# MKRZero_V5_0.net
KiCad netlist of a schematic drawn in EAGLE
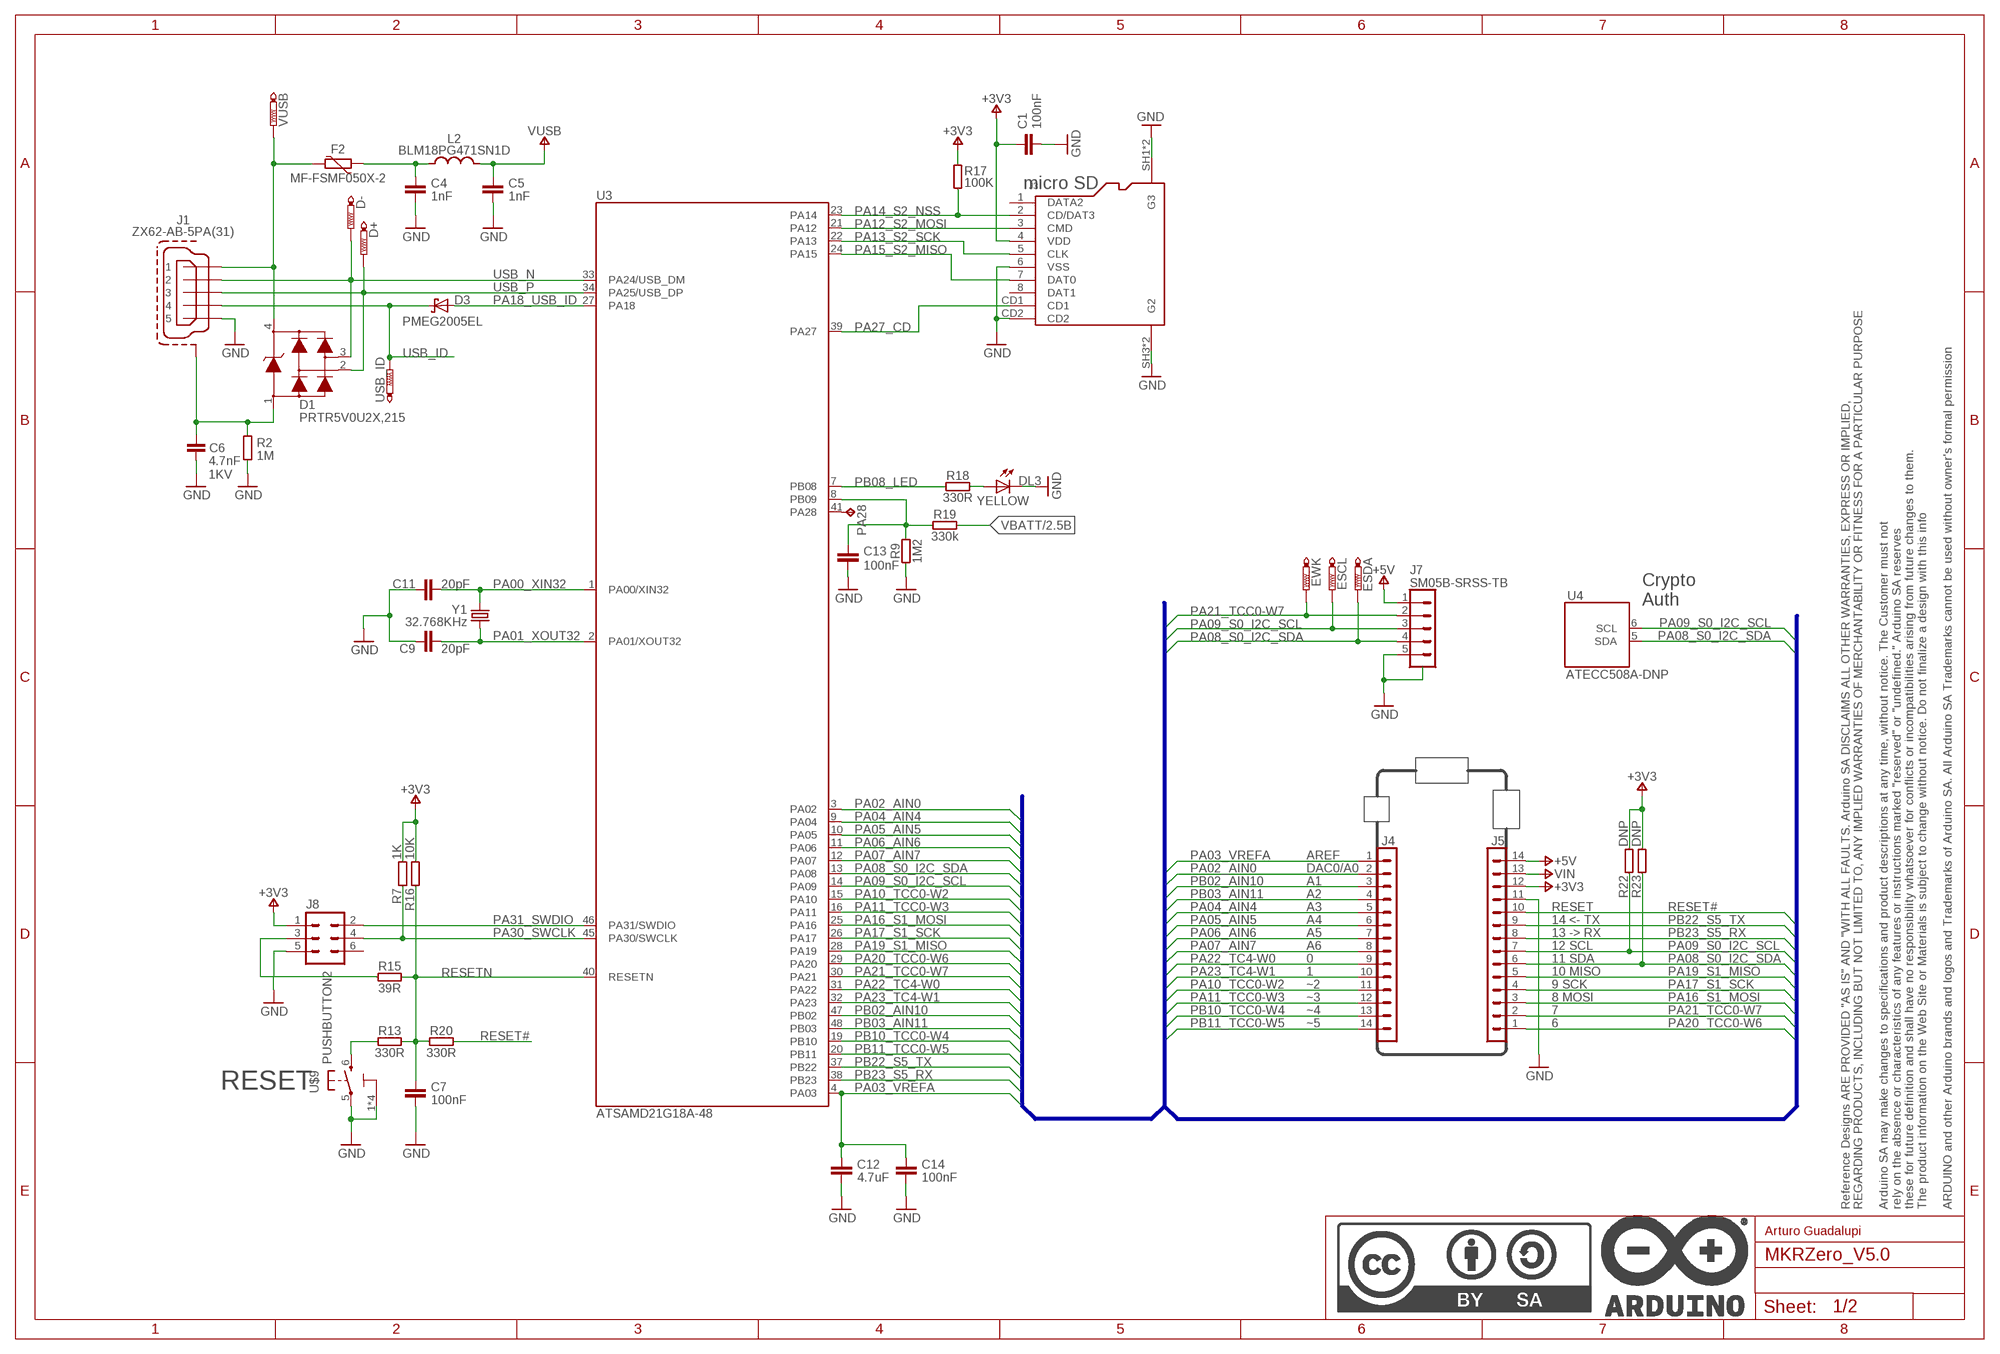
[diagram p0: schematic, sheet 1]
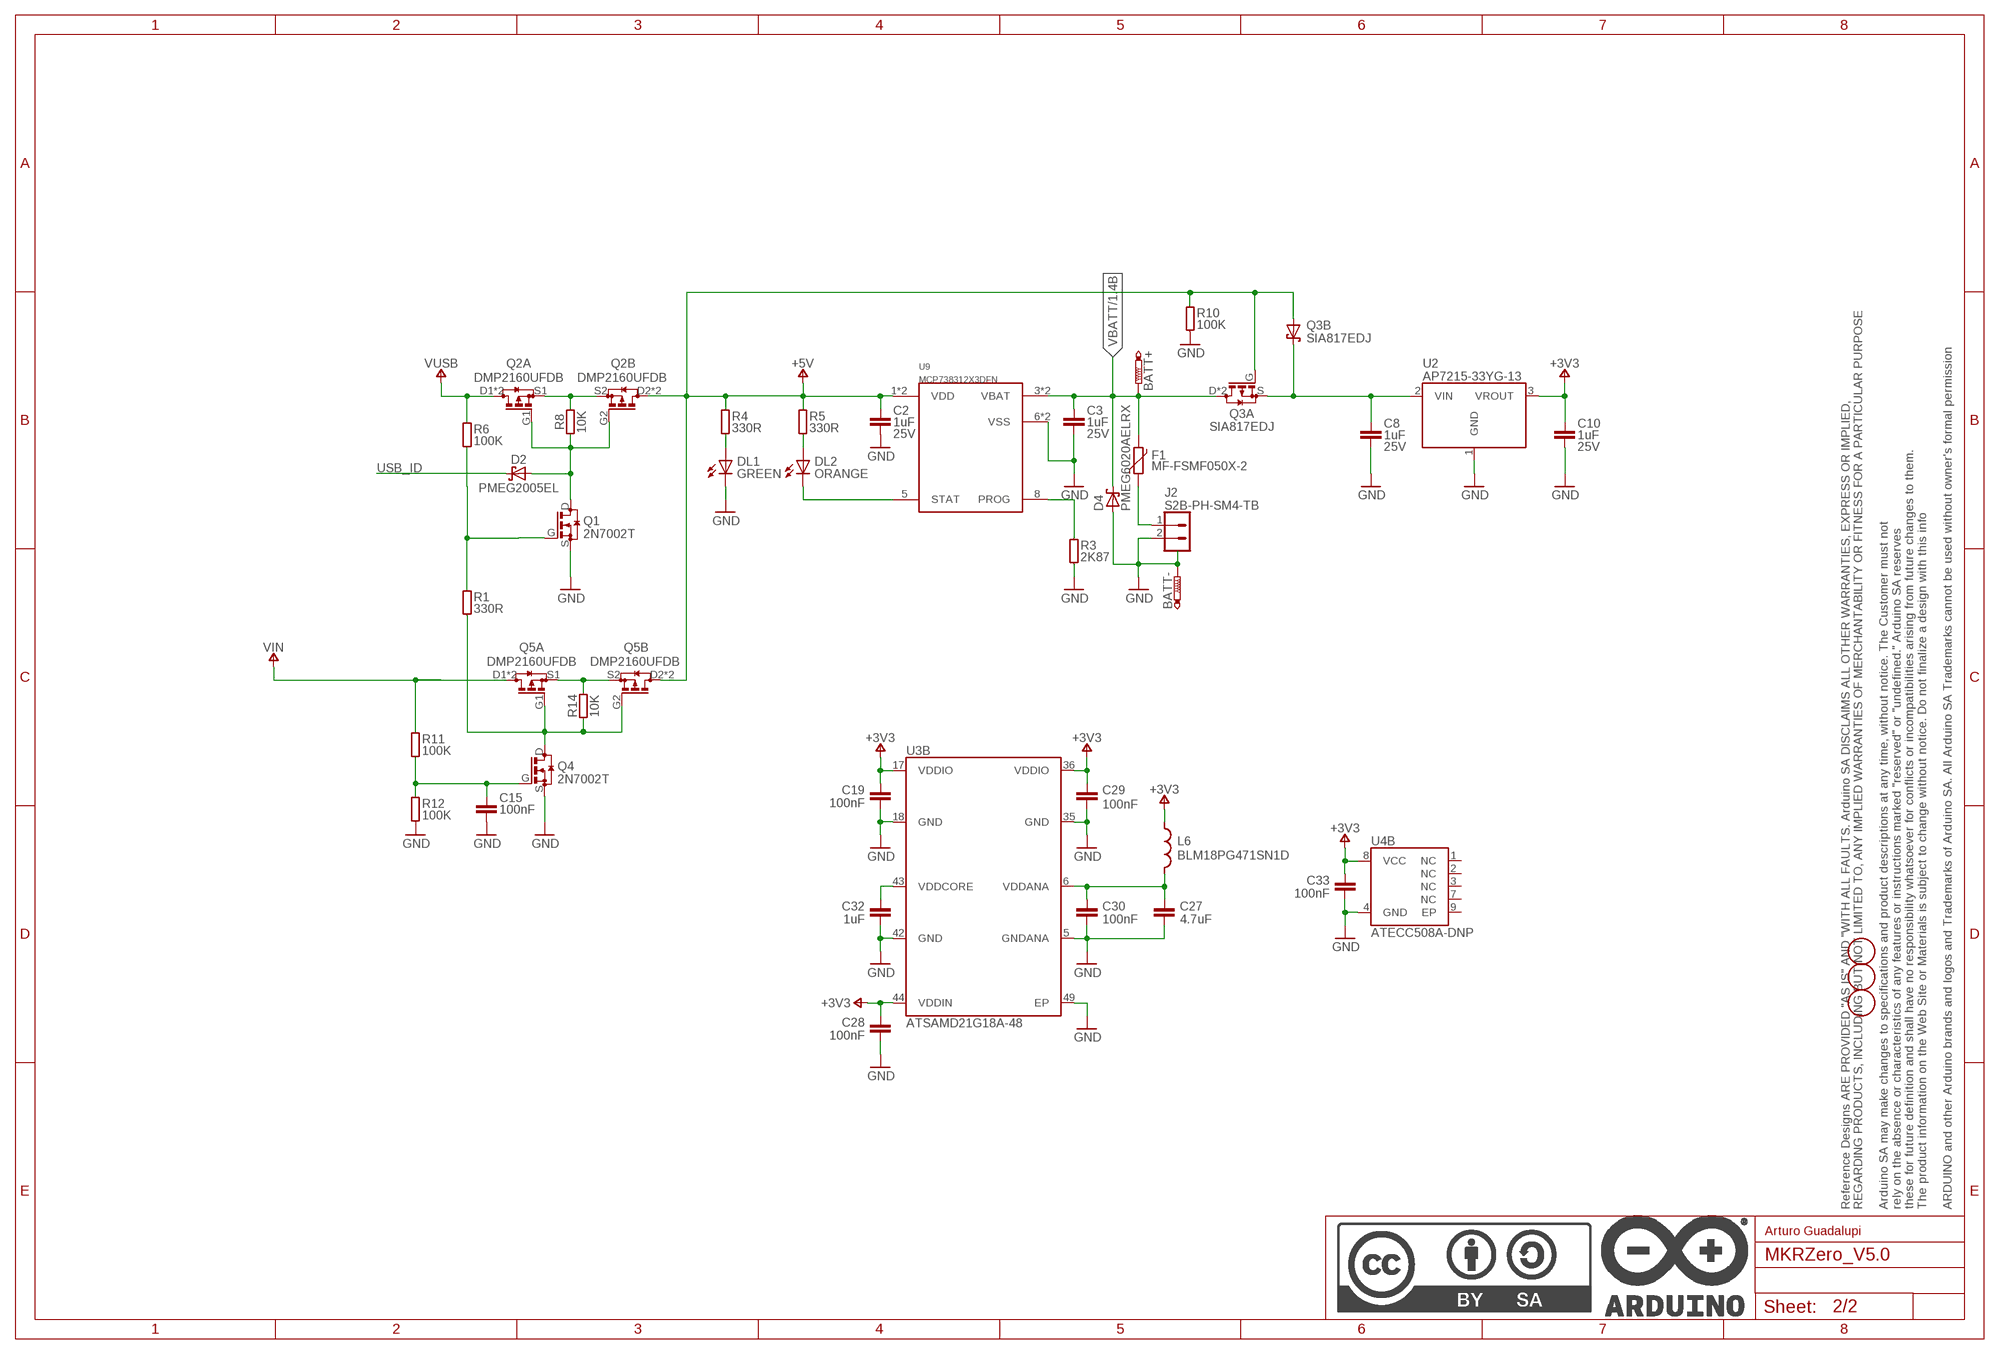
[diagram p1: schematic, sheet 2]

(export (version "E")
  (design (tool "Eeschema 10.0.6"))
  (components
    (comp (ref "BATT+")
      (value "PTR1B1,27")
      (footprint "eagle-import:B1,27")
      (libsource (lib "eagle-import") (part "PTR1B1,27"))
    )
    (comp (ref "BATT-")
      (value "PTR1B1,27")
      (footprint "eagle-import:B1,27")
      (libsource (lib "eagle-import") (part "PTR1B1,27"))
    )
    (comp (ref "C2")
      (value "1uF")
      (footprint "eagle-import:0402-1005X55N")
      (fields
        (field (name "MF") "Murata")
        (field (name "MPN") "GRM155R61E105KA12D ")
        (field (name "VOLTAGE") "25V")
      )
      (libsource (lib "eagle-import") (part "C-0402-1UF"))
    )
    (comp (ref "C3")
      (value "1uF")
      (footprint "eagle-import:0402-1005X55N")
      (fields
        (field (name "MF") "Murata")
        (field (name "MPN") "GRM155R61E105KA12D ")
        (field (name "VOLTAGE") "25V")
      )
      (libsource (lib "eagle-import") (part "C-0402-1UF"))
    )
    (comp (ref "C8")
      (value "1uF")
      (footprint "eagle-import:0402-1005X55N")
      (fields
        (field (name "MF") "Murata")
        (field (name "MPN") "GRM155R61E105KA12D ")
        (field (name "VOLTAGE") "25V")
      )
      (libsource (lib "eagle-import") (part "C-0402-1UF"))
    )
    (comp (ref "C10")
      (value "1uF")
      (footprint "eagle-import:0402-1005X55N")
      (fields
        (field (name "MF") "Murata")
        (field (name "MPN") "GRM155R61E105KA12D ")
        (field (name "VOLTAGE") "25V")
      )
      (libsource (lib "eagle-import") (part "C-0402-1UF"))
    )
    (comp (ref "C15")
      (value "100nF")
      (footprint "eagle-import:0402-1005X55N")
      (fields
        (field (name "MF") "Murata")
        (field (name "MPN") "GRM155R61E105KA12D ")
        (field (name "VOLTAGE") "25V")
      )
      (libsource (lib "eagle-import") (part "C-0402-1UF"))
    )
    (comp (ref "C19")
      (value "100nF")
      (footprint "eagle-import:0402-1005X55N")
      (fields (field (name "MF") "TDK") (field (name "MPN") "C1005X5R1H104K050BB "))
      (libsource (lib "eagle-import") (part "C-0402-100NF"))
    )
    (comp (ref "C27")
      (value "4.7uF")
      (footprint "eagle-import:0402-1005X55N")
      (fields (field (name "MF") "Murata") (field (name "MPN") "GRM155R60J475ME47D "))
      (libsource (lib "eagle-import") (part "C-0402-4.7UF"))
    )
    (comp (ref "C28")
      (value "100nF")
      (footprint "eagle-import:0402-1005X55N")
      (fields (field (name "MF") "TDK") (field (name "MPN") "C1005X5R1H104K050BB "))
      (libsource (lib "eagle-import") (part "C-0402-100NF"))
    )
    (comp (ref "C29")
      (value "100nF")
      (footprint "eagle-import:0402-1005X55N")
      (fields (field (name "MF") "TDK") (field (name "MPN") "C1005X5R1H104K050BB "))
      (libsource (lib "eagle-import") (part "C-0402-100NF"))
    )
    (comp (ref "C30")
      (value "100nF")
      (footprint "eagle-import:0402-1005X55N")
      (fields (field (name "MF") "TDK") (field (name "MPN") "C1005X5R1H104K050BB "))
      (libsource (lib "eagle-import") (part "C-0402-100NF"))
    )
    (comp (ref "C32")
      (value "1uF")
      (footprint "eagle-import:0402-1005X55N")
      (fields (field (name "MF") "Murata") (field (name "MPN") "GRM155R61E105KA12D "))
      (libsource (lib "eagle-import") (part "C-0402-1UF"))
    )
    (comp (ref "C33")
      (value "100nF")
      (footprint "eagle-import:0402-1005X55N")
      (fields (field (name "MF") "TDK") (field (name "MPN") "C1005X5R1H104K050BB "))
      (libsource (lib "eagle-import") (part "C-0402-100NF"))
    )
    (comp (ref "D2")
      (value "PMEG2005EL")
      (footprint "eagle-import:SODFL1008X40N-882D")
      (fields (field (name "MF") "NXP") (field (name "MPN") "PMEG2005EL,315 "))
      (libsource (lib "eagle-import") (part "PMEG2005EL"))
    )
    (comp (ref "D4")
      (value "PMEG6020AELRX")
      (footprint "eagle-import:SMA_DO123")
      (libsource (lib "eagle-import") (part "D_SCHOTTKYSO123"))
    )
    (comp (ref "DL1")
      (value "GREEN")
      (footprint "eagle-import:LEDC1608X80N-AK")
      (fields (field (name "MF") "Avago ") (field (name "MPN") "HSMG-C190 "))
      (libsource (lib "eagle-import") (part "LED-0603-GREEN"))
    )
    (comp (ref "DL2")
      (value "ORANGE")
      (footprint "eagle-import:LEDC1608X80N-AK")
      (fields (field (name "MF") "Avago ") (field (name "MPN") "HSMD-C190 "))
      (libsource (lib "eagle-import") (part "LED-0603-ORANGE"))
    )
    (comp (ref "F1")
      (value "MF-FSMF050X-2")
      (footprint "eagle-import:0603-F1608X100N")
      (fields (field (name "MF") "Bourns Inc ") (field (name "MPN") "MF-FSMF050X-2 "))
      (libsource (lib "eagle-import") (part "MF-FSMF050X-2"))
    )
    (comp (ref "FD1")
      (value "FIDUCIALMOUNT")
      (footprint "eagle-import:FIDUCIAL-MOUNT")
      (libsource (lib "eagle-import") (part "FIDUCIALMOUNT"))
    )
    (comp (ref "FD2")
      (value "FIDUCIALMOUNT")
      (footprint "eagle-import:FIDUCIAL-MOUNT")
      (libsource (lib "eagle-import") (part "FIDUCIALMOUNT"))
    )
    (comp (ref "FD3")
      (value "FIDUCIALMOUNT")
      (footprint "eagle-import:FIDUCIAL-MOUNT")
      (libsource (lib "eagle-import") (part "FIDUCIALMOUNT"))
    )
    (comp (ref "FRAME2")
      (value "DNP")
      (footprint "eagle-import:FRAME")
      (libsource (lib "eagle-import") (part "A3-FRAME"))
    )
    (comp (ref "J2")
      (value "S2B-PH-SM4-TB")
      (footprint "eagle-import:JST-S2B-PH-SM4-TB")
      (fields (field (name "MF") "JST ") (field (name "MPN") "S2B-PH-SM4-TB(LF)(SN) "))
      (libsource (lib "eagle-import") (part "S2B-PH-SM4-TB"))
    )
    (comp (ref "L6")
      (value "BLM18PG471SN1D")
      (footprint "eagle-import:0603-1608X90N")
      (libsource (lib "eagle-import") (part "BLM18PG471SN1D"))
    )
    (comp (ref "Q1")
      (value "2N7002T")
      (footprint "eagle-import:SOTFL50P160X78-3")
      (fields (field (name "MF") "Fairchild"))
      (libsource (lib "eagle-import") (part "2N7002T"))
    )
    (comp (ref "Q2")
      (value "DMP2160UFDB")
      (footprint "eagle-import:SON65P200X200X60-8N-DM")
      (fields (field (name "MF") "Diodes Inc ") (field (name "MPN") "DMP2160UFDB-7 "))
      (libsource (lib "eagle-import") (part "DMP2160UFDB"))
    )
    (comp (ref "Q3")
      (value "SIA817EDJ")
      (footprint "eagle-import:SON65P205X205X75-8N-MWSD")
      (fields (field (name "MF") "Vishay ") (field (name "MPN") "SIA817EDJ-T1-GE3 "))
      (libsource (lib "eagle-import") (part "SIA817EDJ"))
    )
    (comp (ref "Q4")
      (value "2N7002T")
      (footprint "eagle-import:SOTFL50P160X78-3")
      (fields (field (name "MF") "Fairchild"))
      (libsource (lib "eagle-import") (part "2N7002T"))
    )
    (comp (ref "Q5")
      (value "DMP2160UFDB")
      (footprint "eagle-import:SON65P200X200X60-8N-DM")
      (fields (field (name "MF") "Diodes Inc ") (field (name "MPN") "DMP2160UFDB-7 "))
      (libsource (lib "eagle-import") (part "DMP2160UFDB"))
    )
    (comp (ref "R1")
      (value "330R")
      (footprint "eagle-import:0402-1005X55N")
      (fields (field (name "MF") "Yageo ") (field (name "MPN") "RC0402FR-07330RL "))
      (libsource (lib "eagle-import") (part "R-0402-330R"))
    )
    (comp (ref "R3")
      (value "2K87")
      (footprint "eagle-import:0402-1005X55N")
      (fields (field (name "MF") "Yageo") (field (name "MPN") "RC0402FR-072K87L"))
      (libsource (lib "eagle-import") (part "R-0402-2K87"))
    )
    (comp (ref "R4")
      (value "330R")
      (footprint "eagle-import:0402-1005X55N")
      (fields (field (name "MF") "Yageo ") (field (name "MPN") "RC0402FR-07330RL "))
      (libsource (lib "eagle-import") (part "R-0402-330R"))
    )
    (comp (ref "R5")
      (value "330R")
      (footprint "eagle-import:0402-1005X55N")
      (fields (field (name "MF") "Yageo ") (field (name "MPN") "RC0402FR-07330RL "))
      (libsource (lib "eagle-import") (part "R-0402-330R"))
    )
    (comp (ref "R6")
      (value "100K")
      (footprint "eagle-import:0402-1005X55N")
      (fields (field (name "MF") "Yageo ") (field (name "MPN") "RC0402FR-07100KL "))
      (libsource (lib "eagle-import") (part "R-0402-100K"))
    )
    (comp (ref "R8")
      (value "10K")
      (footprint "eagle-import:0402-1005X55N")
      (fields (field (name "MF") "Yageo") (field (name "MPN") "RC0402FR-0710KL"))
      (libsource (lib "eagle-import") (part "R-0402-10K"))
    )
    (comp (ref "R10")
      (value "100K")
      (footprint "eagle-import:0402-1005X55N")
      (fields (field (name "MF") "Yageo ") (field (name "MPN") "RC0402FR-07100KL "))
      (libsource (lib "eagle-import") (part "R-0402-100K"))
    )
    (comp (ref "R11")
      (value "100K")
      (footprint "eagle-import:0402-1005X55N")
      (fields (field (name "MF") "Yageo ") (field (name "MPN") "RC0402FR-07100KL "))
      (libsource (lib "eagle-import") (part "R-0402-100K"))
    )
    (comp (ref "R12")
      (value "100K")
      (footprint "eagle-import:0402-1005X55N")
      (fields (field (name "MF") "Yageo ") (field (name "MPN") "RC0402FR-07100KL "))
      (libsource (lib "eagle-import") (part "R-0402-100K"))
    )
    (comp (ref "R14")
      (value "10K")
      (footprint "eagle-import:0402-1005X55N")
      (fields (field (name "MF") "Yageo") (field (name "MPN") "RC0402FR-0710KL"))
      (libsource (lib "eagle-import") (part "R-0402-10K"))
    )
    (comp (ref "U2")
      (value "AP7215-33YG-13")
      (footprint "eagle-import:SOT150P400X160-3N")
      (fields (field (name "MF") "Diodes Inc ") (field (name "MPN") "AP7215-33YG-13 "))
      (libsource (lib "eagle-import") (part "AP7215-33YG-13"))
    )
    (comp (ref "U3")
      (value "ATSAMD21G18A-48")
      (footprint "eagle-import:QFN50P700X700X90-49XN-EPSQ515")
      (fields (field (name "MF") "Atmel") (field (name "MPN") "ATSAMD21E18A-MU "))
      (libsource (lib "eagle-import") (part "ATSAMD21G18A-48"))
    )
    (comp (ref "U4")
      (value "ATECC508A-DNP")
      (footprint "eagle-import:SON50P300X200X60-9N-EP160X140")
      (fields (field (name "MF") "Atmel") (field (name "MPN") "ATECC508A-MAHDA-T "))
      (libsource (lib "eagle-import") (part "ATECC508A-MAHDA-T"))
    )
    (comp (ref "U9")
      (value "MCP738312X3DFN")
      (footprint "eagle-import:2X3DFN")
      (libsource (lib "eagle-import") (part "MCP738312X3DFN"))
    )
    (comp (ref "C1")
      (value "100nF")
      (footprint "eagle-import:0402-1005X55N")
      (fields (field (name "MF") "TDK") (field (name "MPN") "C1005X5R1H104K050BB "))
      (libsource (lib "eagle-import") (part "C-0402-100NF"))
    )
    (comp (ref "C4")
      (value "1nF")
      (footprint "eagle-import:0402-1005X55N")
      (fields (field (name "MF") "Murata ") (field (name "MPN") "GRM155R71H103KA88J "))
      (libsource (lib "eagle-import") (part "C-0402-10NF"))
    )
    (comp (ref "C5")
      (value "1nF")
      (footprint "eagle-import:0402-1005X55N")
      (fields (field (name "MF") "TDK") (field (name "MPN") "C1005X5R1H104K050BB "))
      (libsource (lib "eagle-import") (part "C-0402-100NF"))
    )
    (comp (ref "C6")
      (value "4.7nF")
      (footprint "eagle-import:C0805")
      (fields (field (name "VOLTAGE") "1KV"))
      (libsource (lib "eagle-import") (part "CAPACITORS-0805"))
    )
    (comp (ref "C7")
      (value "100nF")
      (footprint "eagle-import:0402-1005X55N")
      (fields (field (name "MF") "TDK") (field (name "MPN") "C1005X5R1H104K050BB "))
      (libsource (lib "eagle-import") (part "C-0402-100NF"))
    )
    (comp (ref "C9")
      (value "20pF")
      (footprint "eagle-import:0402-1005X55N")
      (fields (field (name "MF") "Kemet") (field (name "MPN") "CBR04C200J5GAC "))
      (libsource (lib "eagle-import") (part "C-0402-20PF"))
    )
    (comp (ref "C11")
      (value "20pF")
      (footprint "eagle-import:0402-1005X55N")
      (fields (field (name "MF") "Kemet") (field (name "MPN") "CBR04C200J5GAC "))
      (libsource (lib "eagle-import") (part "C-0402-20PF"))
    )
    (comp (ref "C12")
      (value "4.7uF")
      (footprint "eagle-import:0402-1005X55N")
      (fields (field (name "MF") "Murata") (field (name "MPN") "GRM155R60J475ME47D "))
      (libsource (lib "eagle-import") (part "C-0402-4.7UF"))
    )
    (comp (ref "C13")
      (value "100nF")
      (footprint "eagle-import:0402-1005X55N")
      (fields (field (name "MF") "TDK") (field (name "MPN") "C1005X5R1H104K050BB "))
      (libsource (lib "eagle-import") (part "C-0402-100NF"))
    )
    (comp (ref "C14")
      (value "100nF")
      (footprint "eagle-import:0402-1005X55N")
      (fields (field (name "MF") "TDK") (field (name "MPN") "C1005X5R1H104K050BB "))
      (libsource (lib "eagle-import") (part "C-0402-100NF"))
    )
    (comp (ref "D+")
      (value "PTR1B1,27")
      (footprint "eagle-import:B1,27")
      (libsource (lib "eagle-import") (part "PTR1B1,27"))
    )
    (comp (ref "D-")
      (value "PTR1B1,27")
      (footprint "eagle-import:B1,27")
      (libsource (lib "eagle-import") (part "PTR1B1,27"))
    )
    (comp (ref "D1")
      (value "PRTR5V0U2X,215")
      (footprint "eagle-import:SOT190P230X110-4N")
      (fields (field (name "MF") "NXP") (field (name "MPN") "PRTR5V0U2X,215 "))
      (libsource (lib "eagle-import") (part "PRTR5V0U2X,215"))
    )
    (comp (ref "D3")
      (value "PMEG2005EL")
      (footprint "eagle-import:SODFL1008X40N-882D")
      (fields (field (name "MF") "NXP") (field (name "MPN") "PMEG2005EL,315 "))
      (libsource (lib "eagle-import") (part "PMEG2005EL"))
    )
    (comp (ref "DL3")
      (value "YELLOW")
      (footprint "eagle-import:LEDC1608X80N-AK")
      (fields (field (name "MF") "Avago ") (field (name "MPN") "HSMG-C190 "))
      (libsource (lib "eagle-import") (part "LED-0603-GREEN"))
    )
    (comp (ref "ESCL")
      (value "PTR1B1,27")
      (footprint "eagle-import:B1,27")
      (libsource (lib "eagle-import") (part "PTR1B1,27"))
    )
    (comp (ref "ESDA")
      (value "PTR1B1,27")
      (footprint "eagle-import:B1,27")
      (libsource (lib "eagle-import") (part "PTR1B1,27"))
    )
    (comp (ref "EWK")
      (value "PTR1B1,27")
      (footprint "eagle-import:B1,27")
      (libsource (lib "eagle-import") (part "PTR1B1,27"))
    )
    (comp (ref "F2")
      (value "MF-FSMF050X-2")
      (footprint "eagle-import:0603-F1608X100N")
      (fields (field (name "MF") "Bourns Inc ") (field (name "MPN") "MF-FSMF050X-2 "))
      (libsource (lib "eagle-import") (part "MF-FSMF050X-2"))
    )
    (comp (ref "FRAME1")
      (value "DNP")
      (footprint "eagle-import:FRAME")
      (libsource (lib "eagle-import") (part "A3-FRAME"))
    )
    (comp (ref "J1")
      (value "ZX62-AB-5PA(31)")
      (footprint "eagle-import:USBMICRO-ZX62-AB-5PA")
      (libsource (lib "eagle-import") (part "ZX62AB-5PA(11)"))
    )
    (comp (ref "J3")
      (value "AMPHENOL_114-00841-68")
      (footprint "eagle-import:AMPHENOL_114-00841-68")
      (libsource (lib "eagle-import") (part "AMPHENOL_114-00841-68"))
    )
    (comp (ref "J4")
      (value "DNP")
      (footprint "eagle-import:STRIP-14-MODULI-A11")
      (libsource (lib "eagle-import") (part "STRIP-14"))
    )
    (comp (ref "J5")
      (value "DNP")
      (footprint "eagle-import:STRIP-14-MODULI-A11")
      (libsource (lib "eagle-import") (part "STRIP-14"))
    )
    (comp (ref "J7")
      (value "SM05B-SRSS-TB")
      (footprint "eagle-import:SM05B-SRSS-TB")
      (fields (field (name "MF") "JST"))
      (libsource (lib "eagle-import") (part "SM05B-SRSS-TB"))
    )
    (comp (ref "J8")
      (value "2X3_SMD_MALE")
      (footprint "eagle-import:2X3_SMT")
      (libsource (lib "eagle-import") (part "2X3_SMD_MALE"))
    )
    (comp (ref "L2")
      (value "BLM18PG471SN1D")
      (footprint "eagle-import:0603-1608X90N")
      (libsource (lib "eagle-import") (part "BLM18PG471SN1D"))
    )
    (comp (ref "PA28")
      (value "TPB2,54")
      (footprint "eagle-import:B2,54")
      (libsource (lib "eagle-import") (part "TPB2,54"))
    )
    (comp (ref "R2")
      (value "1M")
      (footprint "eagle-import:0402-1005X55N")
      (fields (field (name "MF") "Yageo") (field (name "MPN") "RC0402FR-071ML"))
      (libsource (lib "eagle-import") (part "R-0402-1M"))
    )
    (comp (ref "R7")
      (value "1K")
      (footprint "eagle-import:0402-1005X55N")
      (fields (field (name "MF") "Yageo") (field (name "MPN") "RC0402FR-071KL"))
      (libsource (lib "eagle-import") (part "R-0402-1K"))
    )
    (comp (ref "R9")
      (value "1M2")
      (footprint "eagle-import:0402-1005X55N")
      (fields (field (name "MF") "Yageo ") (field (name "MPN") "RC0402FR-07330RL "))
      (libsource (lib "eagle-import") (part "R-0402-330R"))
    )
    (comp (ref "R13")
      (value "330R")
      (footprint "eagle-import:0402-1005X55N")
      (fields (field (name "MF") "Yageo ") (field (name "MPN") "RC0402FR-07330RL "))
      (libsource (lib "eagle-import") (part "R-0402-330R"))
    )
    (comp (ref "R15")
      (value "39R")
      (footprint "eagle-import:0402-1005X55N")
      (fields (field (name "MF") "Yageo ") (field (name "MPN") "RC0402FR-0739RL "))
      (libsource (lib "eagle-import") (part "R-0402-39R"))
    )
    (comp (ref "R16")
      (value "10K")
      (footprint "eagle-import:0402-1005X55N")
      (fields (field (name "MF") "Yageo") (field (name "MPN") "RC0402FR-0710KL"))
      (libsource (lib "eagle-import") (part "R-0402-10K"))
    )
    (comp (ref "R17")
      (value "100K")
      (footprint "eagle-import:0402-1005X55N")
      (fields (field (name "MF") "Yageo ") (field (name "MPN") "RC0402FR-07100KL "))
      (libsource (lib "eagle-import") (part "R-0402-100K"))
    )
    (comp (ref "R18")
      (value "330R")
      (footprint "eagle-import:0402-1005X55N")
      (fields (field (name "MF") "Yageo ") (field (name "MPN") "RC0402FR-07330RL "))
      (libsource (lib "eagle-import") (part "R-0402-330R"))
    )
    (comp (ref "R19")
      (value "330k")
      (footprint "eagle-import:0402-1005X55N")
      (fields (field (name "MF") "Yageo ") (field (name "MPN") "RC0402FR-07330RL "))
      (libsource (lib "eagle-import") (part "R-0402-330R"))
    )
    (comp (ref "R20")
      (value "330R")
      (footprint "eagle-import:0402-1005X55N")
      (fields (field (name "MF") "Yageo ") (field (name "MPN") "RC0402FR-07330RL "))
      (libsource (lib "eagle-import") (part "R-0402-330R"))
    )
    (comp (ref "R22")
      (value "DNP")
      (footprint "eagle-import:0402-1005X55N")
      (fields (field (name "MF") "Yageo ") (field (name "MPN") "RC0402FR-074K7L "))
      (libsource (lib "eagle-import") (part "R-0402-4K7"))
    )
    (comp (ref "R23")
      (value "DNP")
      (footprint "eagle-import:0402-1005X55N")
      (fields (field (name "MF") "Yageo ") (field (name "MPN") "RC0402FR-074K7L "))
      (libsource (lib "eagle-import") (part "R-0402-4K7"))
    )
    (comp (ref "U$9")
      (value "PUSHBUTTON2")
      (footprint "eagle-import:C&K_PTS820_NOPEGS")
      (libsource (lib "eagle-import") (part "PUSHBUTTON2"))
    )
    (comp (ref "USB_ID")
      (value "PTR1B1,27")
      (footprint "eagle-import:B1,27")
      (libsource (lib "eagle-import") (part "PTR1B1,27"))
    )
    (comp (ref "VUSB")
      (value "PTR1B1,27")
      (footprint "eagle-import:B1,27")
      (libsource (lib "eagle-import") (part "PTR1B1,27"))
    )
    (comp (ref "Y1")
      (value "32.768KHz")
      (footprint "eagle-import:QUARZO-ABS07")
      (fields (field (name "MF") "Abracon ") (field (name "MPN") "ABS07-32.768KHZ-T "))
      (libsource (lib "eagle-import") (part "ABS07-32.768KHZ-T"))
    )
  )
  (nets
    (net (code "1") (name "+3V3") (class "Default")
      (node (ref "C1") (pin "1") (pinfunction "1_1") (pintype "passive"))
      (node (ref "C10") (pin "1") (pinfunction "1_1") (pintype "passive"))
      (node (ref "C19") (pin "1") (pinfunction "1_1") (pintype "passive"))
      (node (ref "C28") (pin "1") (pinfunction "1_1") (pintype "passive"))
      (node (ref "C29") (pin "1") (pinfunction "1_1") (pintype "passive"))
      (node (ref "C33") (pin "1") (pinfunction "1_1") (pintype "passive"))
      (node (ref "J3") (pin "4") (pinfunction "VDD_4") (pintype "power_in"))
      (node (ref "J5") (pin "12") (pinfunction "12_12") (pintype "passive"))
      (node (ref "J8") (pin "1") (pinfunction "1_1") (pintype "passive"))
      (node (ref "L6") (pin "1") (pinfunction "1_1") (pintype "passive"))
      (node (ref "R16") (pin "2") (pinfunction "2_2") (pintype "passive"))
      (node (ref "R17") (pin "2") (pinfunction "2_2") (pintype "passive"))
      (node (ref "R22") (pin "2") (pinfunction "2_2") (pintype "passive"))
      (node (ref "R23") (pin "2") (pinfunction "2_2") (pintype "passive"))
      (node (ref "R7") (pin "2") (pinfunction "2_2") (pintype "passive"))
      (node (ref "U2") (pin "3") (pinfunction "VROUT_3") (pintype "power_in"))
      (node (ref "U3") (pin "17") (pinfunction "VDDIO_17") (pintype "power_in"))
      (node (ref "U3") (pin "36") (pinfunction "VDDIO_36") (pintype "power_in"))
      (node (ref "U3") (pin "44") (pinfunction "VDDIN_44") (pintype "power_in"))
      (node (ref "U4") (pin "8") (pinfunction "VCC_8") (pintype "power_in"))
    )
    (net (code "2") (name "+5V") (class "Default")
      (node (ref "C2") (pin "1") (pinfunction "1_1") (pintype "passive"))
      (node (ref "J5") (pin "14") (pinfunction "14_14") (pintype "passive"))
      (node (ref "J7") (pin "1") (pinfunction "1_1") (pintype "passive"))
      (node (ref "Q2") (pin "D2") (pinfunction "D_D2") (pintype "passive"))
      (node (ref "Q2") (pin "D2'") (pinfunction "D_D2'") (pintype "passive"))
      (node (ref "Q3") (pin "A") (pinfunction "A_A") (pintype "passive"))
      (node (ref "Q3") (pin "G") (pinfunction "G_G") (pintype "passive"))
      (node (ref "Q5") (pin "D2") (pinfunction "D_D2") (pintype "passive"))
      (node (ref "Q5") (pin "D2'") (pinfunction "D_D2'") (pintype "passive"))
      (node (ref "R10") (pin "2") (pinfunction "2_2") (pintype "passive"))
      (node (ref "R4") (pin "2") (pinfunction "2_2") (pintype "passive"))
      (node (ref "R5") (pin "2") (pinfunction "2_2") (pintype "passive"))
      (node (ref "U9") (pin "1") (pinfunction "VDD_1") (pintype "bidirectional"))
      (node (ref "U9") (pin "2") (pinfunction "VDD_2") (pintype "bidirectional"))
    )
    (net (code "3") (name "GND") (class "Default")
      (node (ref "BATT-") (pin "PP") (pinfunction "TP_PP") (pintype "input"))
      (node (ref "C1") (pin "2") (pinfunction "2_2") (pintype "passive"))
      (node (ref "C10") (pin "2") (pinfunction "2_2") (pintype "passive"))
      (node (ref "C11") (pin "1") (pinfunction "1_1") (pintype "passive"))
      (node (ref "C12") (pin "2") (pinfunction "2_2") (pintype "passive"))
      (node (ref "C13") (pin "2") (pinfunction "2_2") (pintype "passive"))
      (node (ref "C14") (pin "2") (pinfunction "2_2") (pintype "passive"))
      (node (ref "C15") (pin "2") (pinfunction "2_2") (pintype "passive"))
      (node (ref "C19") (pin "2") (pinfunction "2_2") (pintype "passive"))
      (node (ref "C2") (pin "2") (pinfunction "2_2") (pintype "passive"))
      (node (ref "C27") (pin "2") (pinfunction "2_2") (pintype "passive"))
      (node (ref "C28") (pin "2") (pinfunction "2_2") (pintype "passive"))
      (node (ref "C29") (pin "2") (pinfunction "2_2") (pintype "passive"))
      (node (ref "C3") (pin "2") (pinfunction "2_2") (pintype "passive"))
      (node (ref "C30") (pin "2") (pinfunction "2_2") (pintype "passive"))
      (node (ref "C32") (pin "2") (pinfunction "2_2") (pintype "passive"))
      (node (ref "C33") (pin "2") (pinfunction "2_2") (pintype "passive"))
      (node (ref "C4") (pin "2") (pinfunction "2_2") (pintype "passive"))
      (node (ref "C5") (pin "2") (pinfunction "2_2") (pintype "passive"))
      (node (ref "C6") (pin "2") (pinfunction "2_2") (pintype "passive"))
      (node (ref "C7") (pin "2") (pinfunction "2_2") (pintype "passive"))
      (node (ref "C8") (pin "2") (pinfunction "2_2") (pintype "passive"))
      (node (ref "C9") (pin "1") (pinfunction "1_1") (pintype "passive"))
      (node (ref "D4") (pin "A") (pinfunction "A_A") (pintype "passive"))
      (node (ref "DL1") (pin "C") (pinfunction "C_C") (pintype "passive"))
      (node (ref "DL3") (pin "C") (pinfunction "C_C") (pintype "passive"))
      (node (ref "J1") (pin "5") (pinfunction "5_5") (pintype "passive"))
      (node (ref "J2") (pin "2") (pinfunction "2_2") (pintype "passive"))
      (node (ref "J2") (pin "3") (pinfunction "SH_3") (pintype "passive"))
      (node (ref "J2") (pin "4") (pinfunction "SH_4") (pintype "passive"))
      (node (ref "J3") (pin "6") (pinfunction "VSS_6") (pintype "power_in"))
      (node (ref "J3") (pin "CD2") (pinfunction "CD2_CD2") (pintype "bidirectional"))
      (node (ref "J3") (pin "SH1") (pinfunction "G3_SH1") (pintype "bidirectional"))
      (node (ref "J3") (pin "SH2") (pinfunction "G3_SH2") (pintype "bidirectional"))
      (node (ref "J3") (pin "SH3") (pinfunction "G2_SH3") (pintype "bidirectional"))
      (node (ref "J3") (pin "SH4") (pinfunction "G2_SH4") (pintype "bidirectional"))
      (node (ref "J5") (pin "11") (pinfunction "11_11") (pintype "passive"))
      (node (ref "J7") (pin "5") (pinfunction "5_5") (pintype "passive"))
      (node (ref "J7") (pin "SH1") (pinfunction "SH_SH1") (pintype "passive"))
      (node (ref "J7") (pin "SH2") (pinfunction "SH_SH2") (pintype "passive"))
      (node (ref "J8") (pin "5") (pinfunction "5_5") (pintype "passive"))
      (node (ref "Q1") (pin "S") (pinfunction "S_S") (pintype "passive"))
      (node (ref "Q4") (pin "S") (pinfunction "S_S") (pintype "passive"))
      (node (ref "R10") (pin "1") (pinfunction "1_1") (pintype "passive"))
      (node (ref "R12") (pin "1") (pinfunction "1_1") (pintype "passive"))
      (node (ref "R2") (pin "1") (pinfunction "1_1") (pintype "passive"))
      (node (ref "R3") (pin "1") (pinfunction "1_1") (pintype "passive"))
      (node (ref "R9") (pin "1") (pinfunction "1_1") (pintype "passive"))
      (node (ref "U$9") (pin "1") (pinfunction "3_1") (pintype "power_in"))
      (node (ref "U$9") (pin "2") (pinfunction "3_2") (pintype "power_in"))
      (node (ref "U$9") (pin "3") (pinfunction "3_3") (pintype "power_in"))
      (node (ref "U$9") (pin "4") (pinfunction "3_4") (pintype "power_in"))
      (node (ref "U$9") (pin "5") (pinfunction "1_5") (pintype "passive"))
      (node (ref "U2") (pin "1") (pinfunction "GND_1") (pintype "power_in"))
      (node (ref "U3") (pin "18") (pinfunction "GND_18") (pintype "power_in"))
      (node (ref "U3") (pin "35") (pinfunction "GND_35") (pintype "power_in"))
      (node (ref "U3") (pin "42") (pinfunction "GND_42") (pintype "power_in"))
      (node (ref "U3") (pin "49") (pinfunction "EP_49") (pintype "passive"))
      (node (ref "U3") (pin "5") (pinfunction "GNDANA_5") (pintype "power_in"))
      (node (ref "U4") (pin "4") (pinfunction "GND_4") (pintype "power_in"))
      (node (ref "U9") (pin "6") (pinfunction "VSS_6") (pintype "bidirectional"))
      (node (ref "U9") (pin "PAD") (pinfunction "VSS_PAD") (pintype "bidirectional"))
    )
    (net (code "4") (name "Net-(C4-Pad1)") (class "Default")
      (node (ref "C4") (pin "1") (pinfunction "1_1") (pintype "passive"))
      (node (ref "F2") (pin "1") (pinfunction "1_1") (pintype "passive"))
      (node (ref "L2") (pin "1") (pinfunction "1_1") (pintype "passive"))
    )
    (net (code "5") (name "Net-(C6-Pad1)") (class "Default")
      (node (ref "C6") (pin "1") (pinfunction "1_1") (pintype "passive"))
      (node (ref "D1") (pin "1") (pinfunction "1_1") (pintype "passive"))
      (node (ref "J1") (pin "10") (pinfunction "SH_10") (pintype "passive"))
      (node (ref "J1") (pin "11") (pinfunction "SH_11") (pintype "passive"))
      (node (ref "J1") (pin "6") (pinfunction "SH_6") (pintype "passive"))
      (node (ref "J1") (pin "7") (pinfunction "SH_7") (pintype "passive"))
      (node (ref "J1") (pin "8") (pinfunction "SH_8") (pintype "passive"))
      (node (ref "J1") (pin "9") (pinfunction "SH_9") (pintype "passive"))
      (node (ref "R2") (pin "2") (pinfunction "2_2") (pintype "passive"))
    )
    (net (code "6") (name "Net-(C15-Pad1)") (class "Default")
      (node (ref "C15") (pin "1") (pinfunction "1_1") (pintype "passive"))
      (node (ref "Q4") (pin "G") (pinfunction "G_G") (pintype "passive"))
      (node (ref "R11") (pin "1") (pinfunction "1_1") (pintype "passive"))
      (node (ref "R12") (pin "2") (pinfunction "2_2") (pintype "passive"))
    )
    (net (code "7") (name "Net-(DL1-PadA)") (class "Default")
      (node (ref "DL1") (pin "A") (pinfunction "A_A") (pintype "passive"))
      (node (ref "R4") (pin "1") (pinfunction "1_1") (pintype "passive"))
    )
    (net (code "8") (name "Net-(DL2-PadA)") (class "Default")
      (node (ref "DL2") (pin "A") (pinfunction "A_A") (pintype "passive"))
      (node (ref "R5") (pin "1") (pinfunction "1_1") (pintype "passive"))
    )
    (net (code "9") (name "Net-(DL3-PadA)") (class "Default")
      (node (ref "DL3") (pin "A") (pinfunction "A_A") (pintype "passive"))
      (node (ref "R18") (pin "2") (pinfunction "2_2") (pintype "passive"))
    )
    (net (code "10") (name "Net-(F1-Pad1)") (class "Default")
      (node (ref "F1") (pin "1") (pinfunction "1_1") (pintype "passive"))
      (node (ref "J2") (pin "1") (pinfunction "1_1") (pintype "passive"))
    )
    (net (code "11") (name "Net-(J8-Pad3)") (class "Default")
      (node (ref "J8") (pin "3") (pinfunction "3_3") (pintype "passive"))
      (node (ref "R15") (pin "1") (pinfunction "1_1") (pintype "passive"))
    )
    (net (code "12") (name "Net-(PA28-TP)") (class "Default")
      (node (ref "PA28") (pin "PP") (pinfunction "TP_PP") (pintype "input"))
      (node (ref "U3") (pin "41") (pinfunction "PA28_41") (pintype "bidirectional"))
    )
    (net (code "13") (name "Net-(Q1-PadG)") (class "Default")
      (node (ref "Q1") (pin "G") (pinfunction "G_G") (pintype "passive"))
      (node (ref "R1") (pin "2") (pinfunction "2_2") (pintype "passive"))
      (node (ref "R6") (pin "1") (pinfunction "1_1") (pintype "passive"))
    )
    (net (code "14") (name "Net-(Q2A-G)") (class "Default")
      (node (ref "D2") (pin "A") (pinfunction "A_A") (pintype "passive"))
      (node (ref "Q1") (pin "D") (pinfunction "D_D") (pintype "passive"))
      (node (ref "Q2") (pin "G1") (pinfunction "G_G1") (pintype "passive"))
      (node (ref "Q2") (pin "G2") (pinfunction "G_G2") (pintype "passive"))
      (node (ref "R8") (pin "1") (pinfunction "1_1") (pintype "passive"))
    )
    (net (code "15") (name "Net-(Q2A-S)") (class "Default")
      (node (ref "Q2") (pin "S1") (pinfunction "S_S1") (pintype "passive"))
      (node (ref "Q2") (pin "S2") (pinfunction "S_S2") (pintype "passive"))
      (node (ref "R8") (pin "2") (pinfunction "2_2") (pintype "passive"))
    )
    (net (code "16") (name "Net-(Q5A-G)") (class "Default")
      (node (ref "Q4") (pin "D") (pinfunction "D_D") (pintype "passive"))
      (node (ref "Q5") (pin "G1") (pinfunction "G_G1") (pintype "passive"))
      (node (ref "Q5") (pin "G2") (pinfunction "G_G2") (pintype "passive"))
      (node (ref "R1") (pin "1") (pinfunction "1_1") (pintype "passive"))
      (node (ref "R14") (pin "1") (pinfunction "1_1") (pintype "passive"))
    )
    (net (code "17") (name "Net-(Q5A-S)") (class "Default")
      (node (ref "Q5") (pin "S1") (pinfunction "S_S1") (pintype "passive"))
      (node (ref "Q5") (pin "S2") (pinfunction "S_S2") (pintype "passive"))
      (node (ref "R14") (pin "2") (pinfunction "2_2") (pintype "passive"))
    )
    (net (code "18") (name "Net-(U$9-2)") (class "Default")
      (node (ref "R13") (pin "1") (pinfunction "1_1") (pintype "passive"))
      (node (ref "U$9") (pin "6") (pinfunction "2_6") (pintype "passive"))
    )
    (net (code "19") (name "Net-(U2-VIN)") (class "Default")
      (node (ref "C8") (pin "1") (pinfunction "1_1") (pintype "passive"))
      (node (ref "Q3") (pin "K") (pinfunction "C_K") (pintype "passive"))
      (node (ref "Q3") (pin "K2") (pinfunction "C_K2") (pintype "passive"))
      (node (ref "Q3") (pin "S") (pinfunction "S_S") (pintype "passive"))
      (node (ref "U2") (pin "2") (pinfunction "VIN_2") (pintype "power_in"))
    )
    (net (code "20") (name "Net-(U3A-PB09)") (class "Default")
      (node (ref "C13") (pin "1") (pinfunction "1_1") (pintype "passive"))
      (node (ref "R19") (pin "1") (pinfunction "1_1") (pintype "passive"))
      (node (ref "R9") (pin "2") (pinfunction "2_2") (pintype "passive"))
      (node (ref "U3") (pin "8") (pinfunction "PB09_8") (pintype "bidirectional"))
    )
    (net (code "21") (name "Net-(U3B-VDDANA)") (class "Default")
      (node (ref "C27") (pin "1") (pinfunction "1_1") (pintype "passive"))
      (node (ref "C30") (pin "1") (pinfunction "1_1") (pintype "passive"))
      (node (ref "L6") (pin "2") (pinfunction "2_2") (pintype "passive"))
      (node (ref "U3") (pin "6") (pinfunction "VDDANA_6") (pintype "power_in"))
    )
    (net (code "22") (name "Net-(U3B-VDDCORE)") (class "Default")
      (node (ref "C32") (pin "1") (pinfunction "1_1") (pintype "passive"))
      (node (ref "U3") (pin "43") (pinfunction "VDDCORE_43") (pintype "power_in"))
    )
    (net (code "23") (name "Net-(U9-PROG)") (class "Default")
      (node (ref "R3") (pin "2") (pinfunction "2_2") (pintype "passive"))
      (node (ref "U9") (pin "8") (pinfunction "PROG_8") (pintype "bidirectional"))
    )
    (net (code "24") (name "Net-(U9-STAT)") (class "Default")
      (node (ref "DL2") (pin "C") (pinfunction "C_C") (pintype "passive"))
      (node (ref "U9") (pin "5") (pinfunction "STAT_5") (pintype "bidirectional"))
    )
    (net (code "25") (name "Net-(VUSB-TP)") (class "Default")
      (node (ref "D1") (pin "4") (pinfunction "4_4") (pintype "passive"))
      (node (ref "F2") (pin "2") (pinfunction "2_2") (pintype "passive"))
      (node (ref "J1") (pin "1") (pinfunction "1_1") (pintype "passive"))
      (node (ref "VUSB") (pin "PP") (pinfunction "TP_PP") (pintype "input"))
    )
    (net (code "26") (name "PA00_XIN32") (class "Default")
      (node (ref "C11") (pin "2") (pinfunction "2_2") (pintype "passive"))
      (node (ref "U3") (pin "1") (pinfunction "PA00/XIN32_1") (pintype "bidirectional"))
      (node (ref "Y1") (pin "2") (pinfunction "2_2") (pintype "passive"))
    )
    (net (code "27") (name "PA01_XOUT32") (class "Default")
      (node (ref "C9") (pin "2") (pinfunction "2_2") (pintype "passive"))
      (node (ref "U3") (pin "2") (pinfunction "PA01/XOUT32_2") (pintype "bidirectional"))
      (node (ref "Y1") (pin "1") (pinfunction "1_1") (pintype "passive"))
    )
    (net (code "28") (name "PA02_AIN0") (class "Default")
      (node (ref "J4") (pin "2") (pinfunction "2_2") (pintype "passive"))
      (node (ref "U3") (pin "3") (pinfunction "PA02_3") (pintype "bidirectional"))
    )
    (net (code "29") (name "PA03_VREFA") (class "Default")
      (node (ref "C12") (pin "1") (pinfunction "1_1") (pintype "passive"))
      (node (ref "C14") (pin "1") (pinfunction "1_1") (pintype "passive"))
      (node (ref "J4") (pin "1") (pinfunction "1_1") (pintype "passive"))
      (node (ref "U3") (pin "4") (pinfunction "PA03_4") (pintype "bidirectional"))
    )
    (net (code "30") (name "PA04_AIN4") (class "Default")
      (node (ref "J4") (pin "5") (pinfunction "5_5") (pintype "passive"))
      (node (ref "U3") (pin "9") (pinfunction "PA04_9") (pintype "bidirectional"))
    )
    (net (code "31") (name "PA05_AIN5") (class "Default")
      (node (ref "J4") (pin "6") (pinfunction "6_6") (pintype "passive"))
      (node (ref "U3") (pin "10") (pinfunction "PA05_10") (pintype "bidirectional"))
    )
    (net (code "32") (name "PA06_AIN6") (class "Default")
      (node (ref "J4") (pin "7") (pinfunction "7_7") (pintype "passive"))
      (node (ref "U3") (pin "11") (pinfunction "PA06_11") (pintype "bidirectional"))
    )
    (net (code "33") (name "PA07_AIN7") (class "Default")
      (node (ref "J4") (pin "8") (pinfunction "8_8") (pintype "passive"))
      (node (ref "U3") (pin "12") (pinfunction "PA07_12") (pintype "bidirectional"))
    )
    (net (code "34") (name "PA08_S0_I2C_SDA") (class "Default")
      (node (ref "ESDA") (pin "PP") (pinfunction "TP_PP") (pintype "input"))
      (node (ref "J5") (pin "6") (pinfunction "6_6") (pintype "passive"))
      (node (ref "J7") (pin "4") (pinfunction "4_4") (pintype "passive"))
      (node (ref "R23") (pin "1") (pinfunction "1_1") (pintype "passive"))
      (node (ref "U3") (pin "13") (pinfunction "PA08_13") (pintype "bidirectional"))
      (node (ref "U4") (pin "5") (pinfunction "SDA_5") (pintype "bidirectional"))
    )
    (net (code "35") (name "PA09_S0_I2C_SCL") (class "Default")
      (node (ref "ESCL") (pin "PP") (pinfunction "TP_PP") (pintype "input"))
      (node (ref "J5") (pin "7") (pinfunction "7_7") (pintype "passive"))
      (node (ref "J7") (pin "3") (pinfunction "3_3") (pintype "passive"))
      (node (ref "R22") (pin "1") (pinfunction "1_1") (pintype "passive"))
      (node (ref "U3") (pin "14") (pinfunction "PA09_14") (pintype "bidirectional"))
      (node (ref "U4") (pin "6") (pinfunction "SCL_6") (pintype "input"))
    )
    (net (code "36") (name "PA10_TCC0-W2") (class "Default")
      (node (ref "J4") (pin "11") (pinfunction "11_11") (pintype "passive"))
      (node (ref "U3") (pin "15") (pinfunction "PA10_15") (pintype "bidirectional"))
    )
    (net (code "37") (name "PA11_TCC0-W3") (class "Default")
      (node (ref "J4") (pin "12") (pinfunction "12_12") (pintype "passive"))
      (node (ref "U3") (pin "16") (pinfunction "PA11_16") (pintype "bidirectional"))
    )
    (net (code "38") (name "PA12_S2_MOSI") (class "Default")
      (node (ref "J3") (pin "3") (pinfunction "CMD_3") (pintype "bidirectional"))
      (node (ref "U3") (pin "21") (pinfunction "PA12_21") (pintype "bidirectional"))
    )
    (net (code "39") (name "PA13_S2_SCK") (class "Default")
      (node (ref "J3") (pin "5") (pinfunction "CLK_5") (pintype "bidirectional"))
      (node (ref "U3") (pin "22") (pinfunction "PA13_22") (pintype "bidirectional"))
    )
    (net (code "40") (name "PA14_S2_NSS") (class "Default")
      (node (ref "J3") (pin "2") (pinfunction "CD/DAT3_2") (pintype "bidirectional"))
      (node (ref "R17") (pin "1") (pinfunction "1_1") (pintype "passive"))
      (node (ref "U3") (pin "23") (pinfunction "PA14_23") (pintype "bidirectional"))
    )
    (net (code "41") (name "PA15_S2_MISO") (class "Default")
      (node (ref "J3") (pin "7") (pinfunction "DAT0_7") (pintype "bidirectional"))
      (node (ref "U3") (pin "24") (pinfunction "PA15_24") (pintype "bidirectional"))
    )
    (net (code "42") (name "PA16_S1_MOSI") (class "Default")
      (node (ref "J5") (pin "3") (pinfunction "3_3") (pintype "passive"))
      (node (ref "U3") (pin "25") (pinfunction "PA16_25") (pintype "bidirectional"))
    )
    (net (code "43") (name "PA17_S1_SCK") (class "Default")
      (node (ref "J5") (pin "4") (pinfunction "4_4") (pintype "passive"))
      (node (ref "U3") (pin "26") (pinfunction "PA17_26") (pintype "bidirectional"))
    )
    (net (code "44") (name "PA18_USB_ID") (class "Default")
      (node (ref "D3") (pin "A") (pinfunction "A_A") (pintype "passive"))
      (node (ref "U3") (pin "27") (pinfunction "PA18_27") (pintype "bidirectional"))
    )
    (net (code "45") (name "PA19_S1_MISO") (class "Default")
      (node (ref "J5") (pin "5") (pinfunction "5_5") (pintype "passive"))
      (node (ref "U3") (pin "28") (pinfunction "PA19_28") (pintype "bidirectional"))
    )
    (net (code "46") (name "PA20_TCC0-W6") (class "Default")
      (node (ref "J5") (pin "1") (pinfunction "1_1") (pintype "passive"))
      (node (ref "U3") (pin "29") (pinfunction "PA20_29") (pintype "bidirectional"))
    )
    (net (code "47") (name "PA21_TCC0-W7") (class "Default")
      (node (ref "EWK") (pin "PP") (pinfunction "TP_PP") (pintype "input"))
      (node (ref "J5") (pin "2") (pinfunction "2_2") (pintype "passive"))
      (node (ref "J7") (pin "2") (pinfunction "2_2") (pintype "passive"))
      (node (ref "U3") (pin "30") (pinfunction "PA21_30") (pintype "bidirectional"))
    )
    (net (code "48") (name "PA22_TC4-W0") (class "Default")
      (node (ref "J4") (pin "9") (pinfunction "9_9") (pintype "passive"))
      (node (ref "U3") (pin "31") (pinfunction "PA22_31") (pintype "bidirectional"))
    )
    (net (code "49") (name "PA23_TC4-W1") (class "Default")
      (node (ref "J4") (pin "10") (pinfunction "10_10") (pintype "passive"))
      (node (ref "U3") (pin "32") (pinfunction "PA23_32") (pintype "bidirectional"))
    )
    (net (code "50") (name "PA27_CD") (class "Default")
      (node (ref "J3") (pin "CD1") (pinfunction "CD1_CD1") (pintype "bidirectional"))
      (node (ref "U3") (pin "39") (pinfunction "PA27_39") (pintype "bidirectional"))
    )
    (net (code "51") (name "PA30_SWCLK") (class "Default")
      (node (ref "J8") (pin "4") (pinfunction "4_4") (pintype "passive"))
      (node (ref "R7") (pin "1") (pinfunction "1_1") (pintype "passive"))
      (node (ref "U3") (pin "45") (pinfunction "PA30/SWCLK_45") (pintype "bidirectional"))
    )
    (net (code "52") (name "PA31_SWDIO") (class "Default")
      (node (ref "J8") (pin "2") (pinfunction "2_2") (pintype "passive"))
      (node (ref "U3") (pin "46") (pinfunction "PA31/SWDIO_46") (pintype "bidirectional"))
    )
    (net (code "53") (name "PB02_AIN10") (class "Default")
      (node (ref "J4") (pin "3") (pinfunction "3_3") (pintype "passive"))
      (node (ref "U3") (pin "47") (pinfunction "PB02_47") (pintype "bidirectional"))
    )
    (net (code "54") (name "PB03_AIN11") (class "Default")
      (node (ref "J4") (pin "4") (pinfunction "4_4") (pintype "passive"))
      (node (ref "U3") (pin "48") (pinfunction "PB03_48") (pintype "bidirectional"))
    )
    (net (code "55") (name "PB08_LED") (class "Default")
      (node (ref "R18") (pin "1") (pinfunction "1_1") (pintype "passive"))
      (node (ref "U3") (pin "7") (pinfunction "PB08_7") (pintype "bidirectional"))
    )
    (net (code "56") (name "PB10_TCC0-W4") (class "Default")
      (node (ref "J4") (pin "13") (pinfunction "13_13") (pintype "passive"))
      (node (ref "U3") (pin "19") (pinfunction "PB10_19") (pintype "bidirectional"))
    )
    (net (code "57") (name "PB11_TCC0-W5") (class "Default")
      (node (ref "J4") (pin "14") (pinfunction "14_14") (pintype "passive"))
      (node (ref "U3") (pin "20") (pinfunction "PB11_20") (pintype "bidirectional"))
    )
    (net (code "58") (name "PB22_S5_TX") (class "Default")
      (node (ref "J5") (pin "9") (pinfunction "9_9") (pintype "passive"))
      (node (ref "U3") (pin "37") (pinfunction "PB22_37") (pintype "bidirectional"))
    )
    (net (code "59") (name "PB23_S5_RX") (class "Default")
      (node (ref "J5") (pin "8") (pinfunction "8_8") (pintype "passive"))
      (node (ref "U3") (pin "38") (pinfunction "PB23_38") (pintype "bidirectional"))
    )
    (net (code "60") (name "RESET#") (class "Default")
      (node (ref "J5") (pin "10") (pinfunction "10_10") (pintype "passive"))
      (node (ref "R20") (pin "2") (pinfunction "2_2") (pintype "passive"))
    )
    (net (code "61") (name "RESETN") (class "Default")
      (node (ref "C7") (pin "1") (pinfunction "1_1") (pintype "passive"))
      (node (ref "R13") (pin "2") (pinfunction "2_2") (pintype "passive"))
      (node (ref "R15") (pin "2") (pinfunction "2_2") (pintype "passive"))
      (node (ref "R16") (pin "1") (pinfunction "1_1") (pintype "passive"))
      (node (ref "R20") (pin "1") (pinfunction "1_1") (pintype "passive"))
      (node (ref "U3") (pin "40") (pinfunction "RESETN_40") (pintype "bidirectional"))
    )
    (net (code "62") (name "USB_ID") (class "Default")
      (node (ref "D2") (pin "C") (pinfunction "C_C") (pintype "passive"))
      (node (ref "D3") (pin "C") (pinfunction "C_C") (pintype "passive"))
      (node (ref "J1") (pin "4") (pinfunction "4_4") (pintype "passive"))
      (node (ref "USB_ID") (pin "PP") (pinfunction "TP_PP") (pintype "input"))
    )
    (net (code "63") (name "USB_N") (class "Default")
      (node (ref "D-") (pin "PP") (pinfunction "TP_PP") (pintype "input"))
      (node (ref "D1") (pin "3") (pinfunction "3_3") (pintype "passive"))
      (node (ref "J1") (pin "2") (pinfunction "2_2") (pintype "passive"))
      (node (ref "U3") (pin "33") (pinfunction "PA24/USB_DM_33") (pintype "bidirectional"))
    )
    (net (code "64") (name "USB_P") (class "Default")
      (node (ref "D+") (pin "PP") (pinfunction "TP_PP") (pintype "input"))
      (node (ref "D1") (pin "2") (pinfunction "2_2") (pintype "passive"))
      (node (ref "J1") (pin "3") (pinfunction "3_3") (pintype "passive"))
      (node (ref "U3") (pin "34") (pinfunction "PA25/USB_DP_34") (pintype "bidirectional"))
    )
    (net (code "65") (name "VBATT") (class "Default")
      (node (ref "BATT+") (pin "PP") (pinfunction "TP_PP") (pintype "input"))
      (node (ref "C3") (pin "1") (pinfunction "1_1") (pintype "passive"))
      (node (ref "D4") (pin "C") (pinfunction "C_C") (pintype "passive"))
      (node (ref "F1") (pin "2") (pinfunction "2_2") (pintype "passive"))
      (node (ref "Q3") (pin "D") (pinfunction "D_D") (pintype "passive"))
      (node (ref "Q3") (pin "D2") (pinfunction "D_D2") (pintype "passive"))
      (node (ref "R19") (pin "2") (pinfunction "2_2") (pintype "passive"))
      (node (ref "U9") (pin "3") (pinfunction "VBAT_3") (pintype "bidirectional"))
      (node (ref "U9") (pin "4") (pinfunction "VBAT_4") (pintype "bidirectional"))
    )
    (net (code "66") (name "VIN") (class "Default")
      (node (ref "J5") (pin "13") (pinfunction "13_13") (pintype "passive"))
      (node (ref "Q5") (pin "D1") (pinfunction "D_D1") (pintype "passive"))
      (node (ref "Q5") (pin "D1'") (pinfunction "D_D1'") (pintype "passive"))
      (node (ref "R11") (pin "2") (pinfunction "2_2") (pintype "passive"))
    )
    (net (code "67") (name "VUSB") (class "Default")
      (node (ref "C5") (pin "1") (pinfunction "1_1") (pintype "passive"))
      (node (ref "L2") (pin "2") (pinfunction "2_2") (pintype "passive"))
      (node (ref "Q2") (pin "D1") (pinfunction "D_D1") (pintype "passive"))
      (node (ref "Q2") (pin "D1'") (pinfunction "D_D1'") (pintype "passive"))
      (node (ref "R6") (pin "2") (pinfunction "2_2") (pintype "passive"))
    )
    (net (code "68") (name "unconnected-(J3-DAT1-Pad8)") (class "Default")
      (node (ref "J3") (pin "8") (pinfunction "DAT1_8") (pintype "bidirectional"))
    )
    (net (code "69") (name "unconnected-(J3-DATA2-Pad1)") (class "Default")
      (node (ref "J3") (pin "1") (pinfunction "DATA2_1") (pintype "bidirectional"))
    )
    (net (code "70") (name "unconnected-(J8-Pad6)") (class "Default")
      (node (ref "J8") (pin "6") (pinfunction "6_6") (pintype "passive"))
    )
    (net (code "71") (name "unconnected-(U4B-EP-Pad9)") (class "Default")
      (node (ref "U4") (pin "9") (pinfunction "EP_9") (pintype "passive"))
    )
    (net (code "72") (name "unconnected-(U4B-NC-Pad1)") (class "Default")
      (node (ref "U4") (pin "1") (pinfunction "NC_1") (pintype "bidirectional"))
    )
    (net (code "73") (name "unconnected-(U4B-NC-Pad2)") (class "Default")
      (node (ref "U4") (pin "2") (pinfunction "NC_2") (pintype "bidirectional"))
    )
    (net (code "74") (name "unconnected-(U4B-NC-Pad3)") (class "Default")
      (node (ref "U4") (pin "3") (pinfunction "NC_3") (pintype "bidirectional"))
    )
    (net (code "75") (name "unconnected-(U4B-NC-Pad7)") (class "Default")
      (node (ref "U4") (pin "7") (pinfunction "NC_7") (pintype "bidirectional"))
    )
  )
)
